# Baro.net
KiCad netlist of a schematic drawn in EAGLE
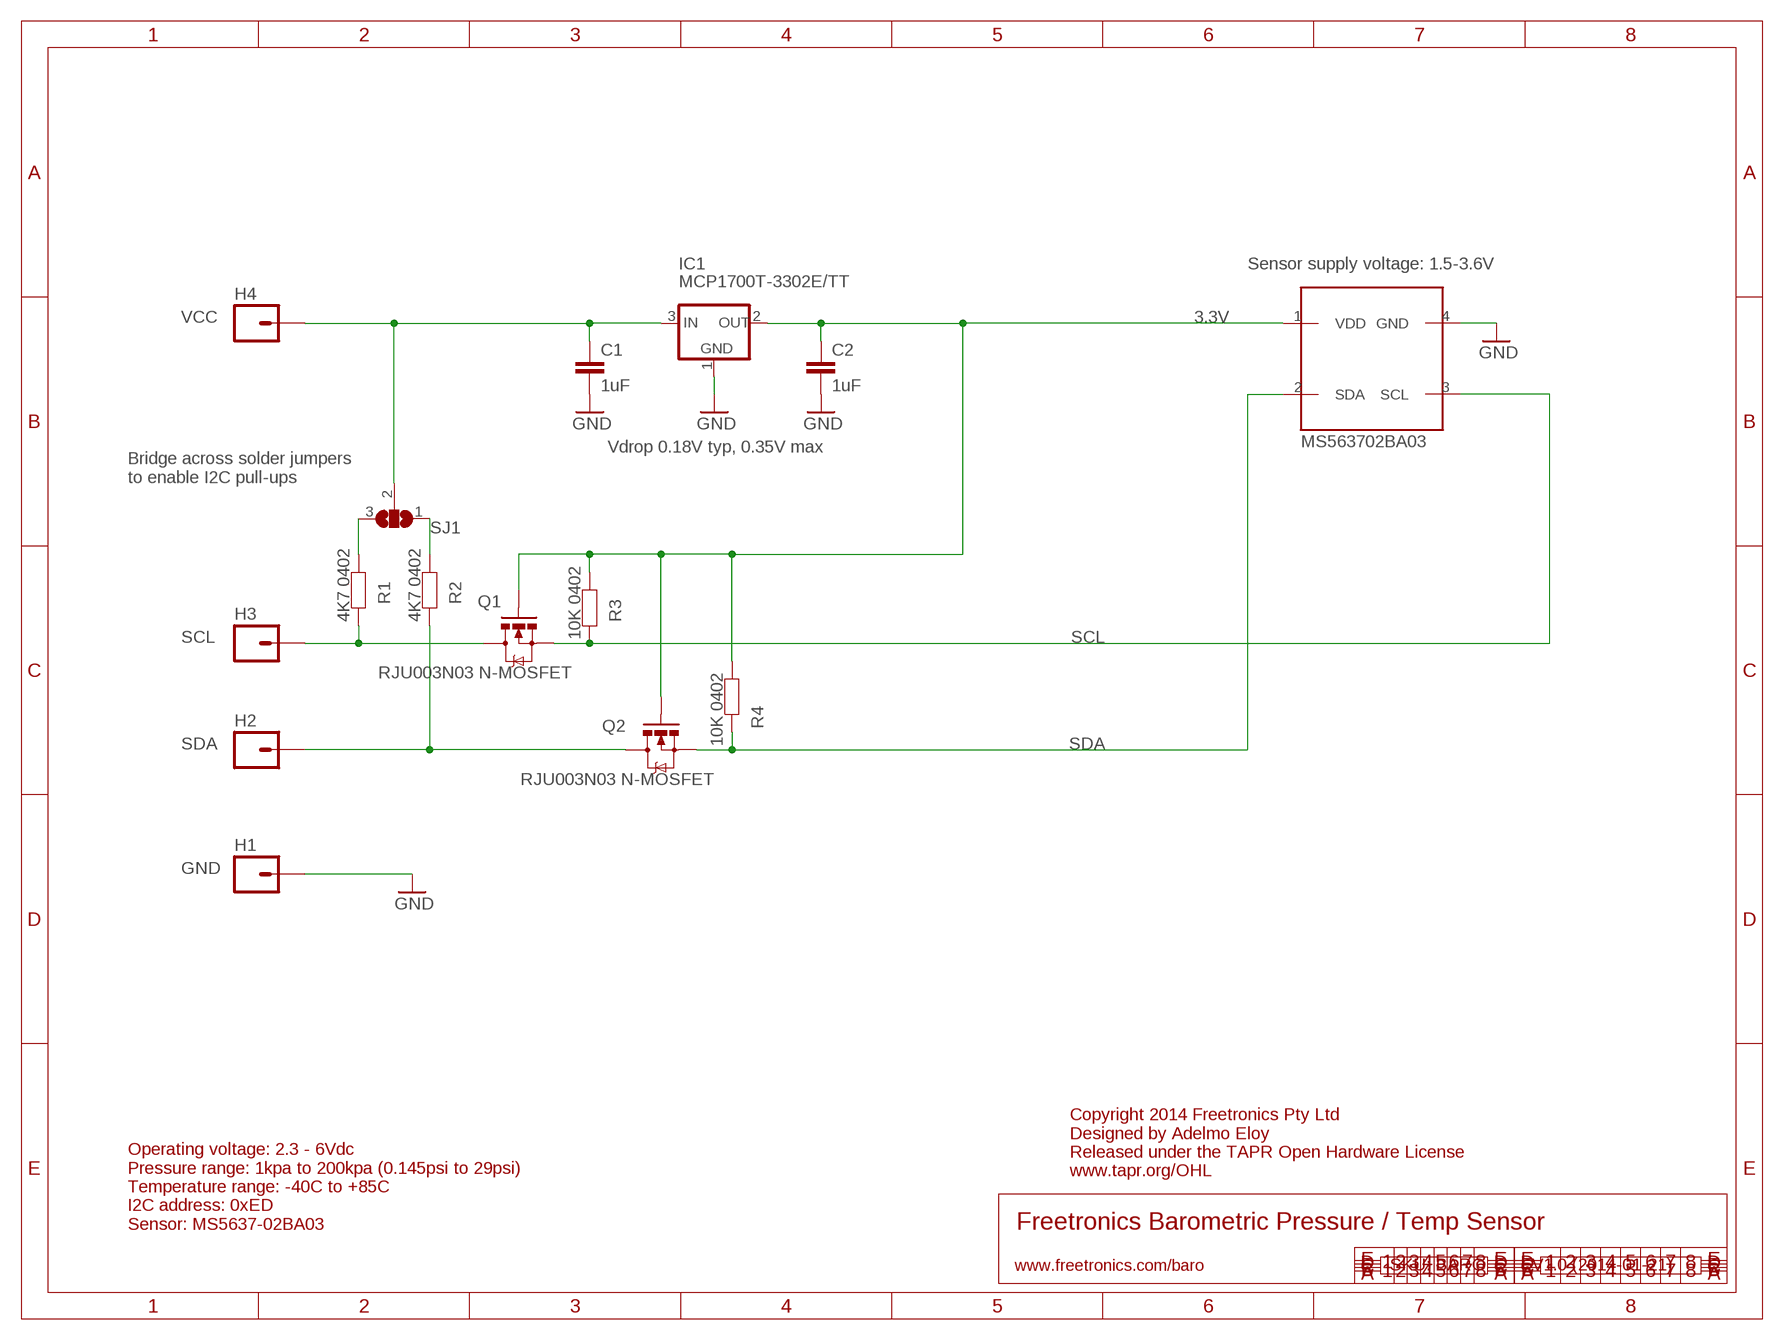
[diagram p0: schematic, sheet 1]

(export (version "E")
  (design (tool "Eeschema 10.0.6"))
  (components
    (comp (ref "C1")
      (value "1uF")
      (footprint "eagle-import:0603")
      (libsource (lib "eagle-import") (part "CAP0603"))
    )
    (comp (ref "C2")
      (value "1uF")
      (footprint "eagle-import:0603")
      (libsource (lib "eagle-import") (part "CAP0603"))
    )
    (comp (ref "H1")
      (value "GND")
      (footprint "eagle-import:1X01")
      (libsource (lib "eagle-import") (part "M01PTH"))
    )
    (comp (ref "H2")
      (value "SDA")
      (footprint "eagle-import:1X01")
      (libsource (lib "eagle-import") (part "M01PTH"))
    )
    (comp (ref "H3")
      (value "SCL")
      (footprint "eagle-import:1X01")
      (libsource (lib "eagle-import") (part "M01PTH"))
    )
    (comp (ref "H4")
      (value "VCC")
      (footprint "eagle-import:1X01")
      (libsource (lib "eagle-import") (part "M01PTH"))
    )
    (comp (ref "IC1")
      (value "MCP1700T-3302E/TT")
      (footprint "eagle-import:SOT23-3")
      (libsource (lib "eagle-import") (part "V_REG_78XXSOT23-3"))
    )
    (comp (ref "IC2")
      (value "MS563702BA03")
      (footprint "eagle-import:MS5637")
      (libsource (lib "eagle-import") (part "MS563702BA03"))
    )
    (comp (ref "Q1")
      (value "RJU003N03 N-MOSFET")
      (footprint "eagle-import:SOT32-3")
      (libsource (lib "eagle-import") (part "MOSFET-NSOT-323"))
    )
    (comp (ref "Q2")
      (value "RJU003N03 N-MOSFET")
      (footprint "eagle-import:SOT32-3")
      (libsource (lib "eagle-import") (part "MOSFET-NSOT-323"))
    )
    (comp (ref "R1")
      (value "4K7 0402")
      (footprint "eagle-import:0402")
      (libsource (lib "eagle-import") (part "RESISTOR0402"))
    )
    (comp (ref "R2")
      (value "4K7 0402")
      (footprint "eagle-import:0402")
      (libsource (lib "eagle-import") (part "RESISTOR0402"))
    )
    (comp (ref "R3")
      (value "10K 0402")
      (footprint "eagle-import:0402")
      (libsource (lib "eagle-import") (part "RESISTOR0402"))
    )
    (comp (ref "R4")
      (value "10K 0402")
      (footprint "eagle-import:0402")
      (libsource (lib "eagle-import") (part "RESISTOR0402"))
    )
    (comp (ref "SJ1")
      (value "SJ2W")
      (footprint "eagle-import:SJ_2")
      (libsource (lib "eagle-import") (part "SJ2W"))
    )
  )
  (nets
    (net (code "1") (name "/3.3V") (class "Default")
      (node (ref "C2") (pin "1") (pinfunction "1_1") (pintype "passive"))
      (node (ref "IC1") (pin "2") (pinfunction "OUT_2") (pintype "output"))
      (node (ref "IC2") (pin "1") (pinfunction "VDD_1") (pintype "bidirectional"))
      (node (ref "Q1") (pin "1") (pinfunction "G_1") (pintype "passive"))
      (node (ref "Q2") (pin "1") (pinfunction "G_1") (pintype "passive"))
      (node (ref "R3") (pin "2") (pinfunction "2_2") (pintype "passive"))
      (node (ref "R4") (pin "2") (pinfunction "2_2") (pintype "passive"))
    )
    (net (code "2") (name "/SCL") (class "Default")
      (node (ref "H3") (pin "1") (pinfunction "1_1") (pintype "passive"))
      (node (ref "Q1") (pin "3") (pinfunction "D_3") (pintype "passive"))
      (node (ref "R1") (pin "1") (pinfunction "1_1") (pintype "passive"))
    )
    (net (code "3") (name "/SDA") (class "Default")
      (node (ref "H2") (pin "1") (pinfunction "1_1") (pintype "passive"))
      (node (ref "Q2") (pin "3") (pinfunction "D_3") (pintype "passive"))
      (node (ref "R2") (pin "1") (pinfunction "1_1") (pintype "passive"))
    )
    (net (code "4") (name "GND") (class "Default")
      (node (ref "C1") (pin "2") (pinfunction "2_2") (pintype "passive"))
      (node (ref "C2") (pin "2") (pinfunction "2_2") (pintype "passive"))
      (node (ref "H1") (pin "1") (pinfunction "1_1") (pintype "passive"))
      (node (ref "IC1") (pin "1") (pinfunction "GND_1") (pintype "input"))
      (node (ref "IC2") (pin "4") (pinfunction "GND_4") (pintype "bidirectional"))
    )
    (net (code "5") (name "Net-(IC1-IN)") (class "Default")
      (node (ref "C1") (pin "1") (pinfunction "1_1") (pintype "passive"))
      (node (ref "H4") (pin "1") (pinfunction "1_1") (pintype "passive"))
      (node (ref "IC1") (pin "3") (pinfunction "IN_3") (pintype "input"))
      (node (ref "SJ1") (pin "2") (pinfunction "2_2") (pintype "passive"))
    )
    (net (code "6") (name "Net-(IC2-SCL)") (class "Default")
      (node (ref "IC2") (pin "3") (pinfunction "SCL_3") (pintype "bidirectional"))
      (node (ref "Q1") (pin "2") (pinfunction "S_2") (pintype "passive"))
      (node (ref "R3") (pin "1") (pinfunction "1_1") (pintype "passive"))
    )
    (net (code "7") (name "Net-(IC2-SDA)") (class "Default")
      (node (ref "IC2") (pin "2") (pinfunction "SDA_2") (pintype "bidirectional"))
      (node (ref "Q2") (pin "2") (pinfunction "S_2") (pintype "passive"))
      (node (ref "R4") (pin "1") (pinfunction "1_1") (pintype "passive"))
    )
    (net (code "8") (name "Net-(R1-Pad2)") (class "Default")
      (node (ref "R1") (pin "2") (pinfunction "2_2") (pintype "passive"))
      (node (ref "SJ1") (pin "3") (pinfunction "3_3") (pintype "passive"))
    )
    (net (code "9") (name "Net-(R2-Pad2)") (class "Default")
      (node (ref "R2") (pin "2") (pinfunction "2_2") (pintype "passive"))
      (node (ref "SJ1") (pin "1") (pinfunction "1_1") (pintype "passive"))
    )
  )
)
